# SML-230109PCB1__MCU.net
KiCad netlist of a schematic drawn in Altium Designer
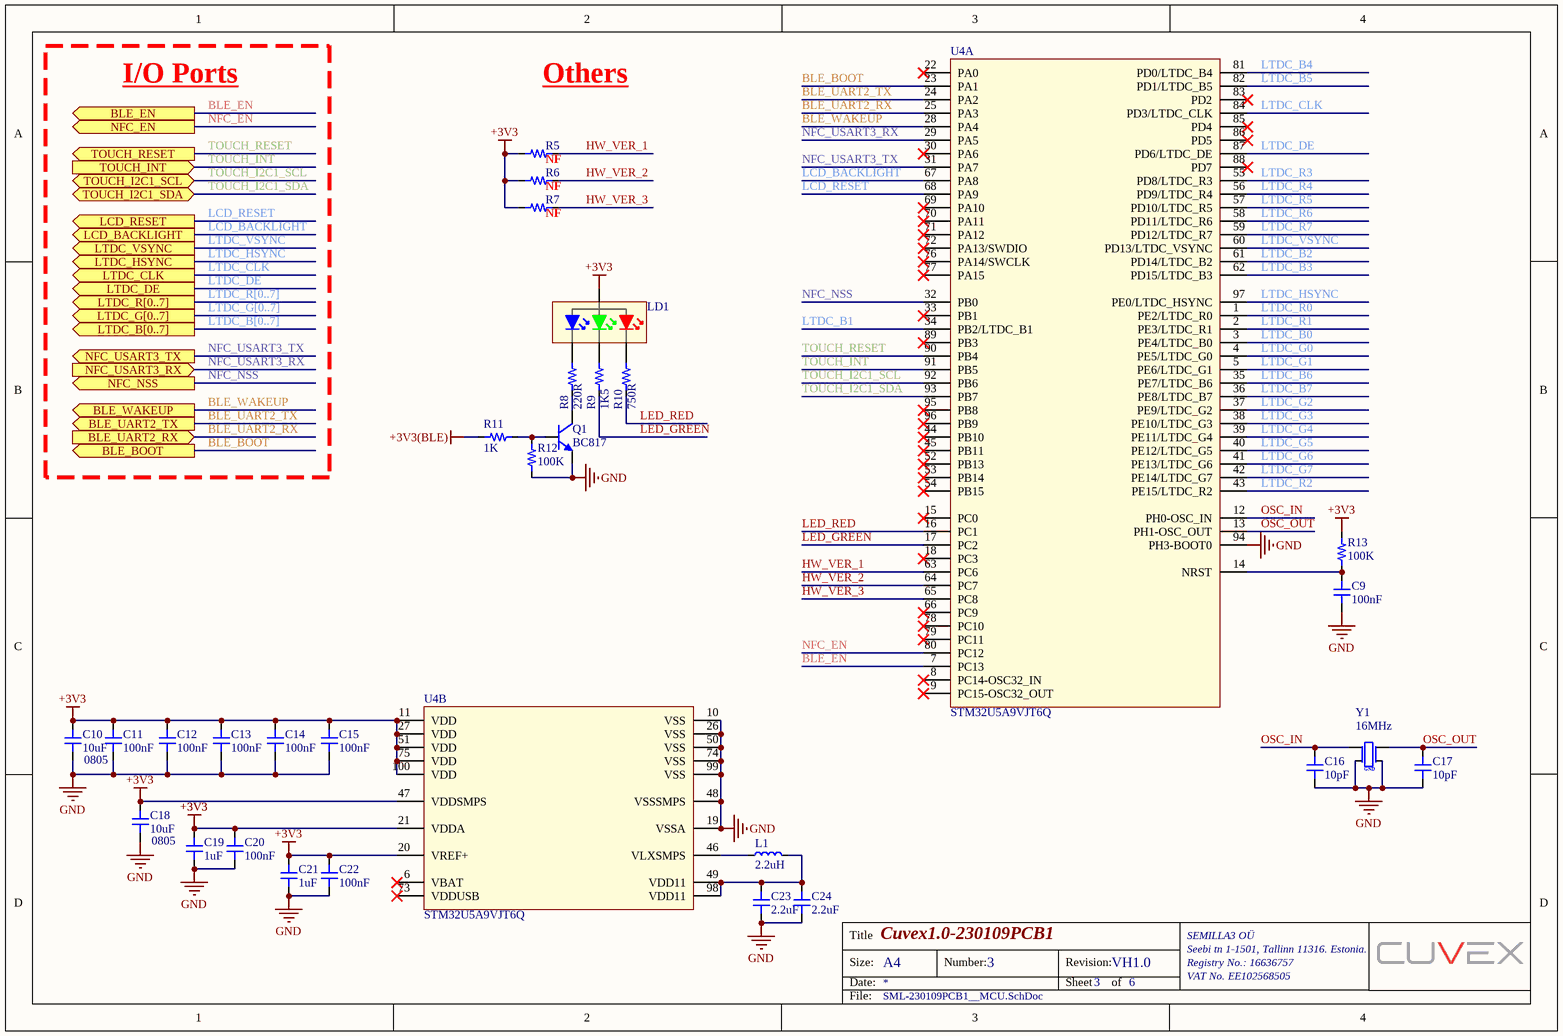
[diagram p0: SML-230109PCB1__MCU.SchDoc]

(export (version "E")
  (design (tool "Eeschema 10.0.6"))
  (components
    (comp (ref "C9")
      (value "100nF")
      (footprint "[G] CAP-MLCC__0603")
      (description "CAP MLCC 0603")
      (fields (field (name "VOLTAGE") "010") (field (name "Comment") "."))
      (libsource (lib "DEB_LIB_SCH_22-03") (part "CAP_MLCC_0603"))
    )
    (comp (ref "C10")
      (value "10uF")
      (footprint "[G] CAP-MLCC__0805")
      (description "CAP MLCC 0805")
      (fields
        (field (name "VOLTAGE") "010")
        (field (name "[06] - PACKAGE") "0805")
        (field (name "Comment") ".")
      )
      (libsource (lib "DEB_LIB_SCH_22-03") (part "CAP_MLCC_0805"))
    )
    (comp (ref "C11")
      (value "100nF")
      (footprint "[G] CAP-MLCC__0603")
      (description "CAP MLCC 0603")
      (fields (field (name "VOLTAGE") "010") (field (name "Comment") "."))
      (libsource (lib "DEB_LIB_SCH_22-03") (part "CAP_MLCC_0603"))
    )
    (comp (ref "C12")
      (value "100nF")
      (footprint "[G] CAP-MLCC__0603")
      (description "CAP MLCC 0603")
      (fields (field (name "VOLTAGE") "010") (field (name "Comment") "."))
      (libsource (lib "DEB_LIB_SCH_22-03") (part "CAP_MLCC_0603"))
    )
    (comp (ref "C13")
      (value "100nF")
      (footprint "[G] CAP-MLCC__0603")
      (description "CAP MLCC 0603")
      (fields (field (name "VOLTAGE") "010") (field (name "Comment") "."))
      (libsource (lib "DEB_LIB_SCH_22-03") (part "CAP_MLCC_0603"))
    )
    (comp (ref "C14")
      (value "100nF")
      (footprint "[G] CAP-MLCC__0603")
      (description "CAP MLCC 0603")
      (fields (field (name "VOLTAGE") "010") (field (name "Comment") "."))
      (libsource (lib "DEB_LIB_SCH_22-03") (part "CAP_MLCC_0603"))
    )
    (comp (ref "C15")
      (value "100nF")
      (footprint "[G] CAP-MLCC__0603")
      (description "CAP MLCC 0603")
      (fields (field (name "VOLTAGE") "010") (field (name "Comment") "."))
      (libsource (lib "DEB_LIB_SCH_22-03") (part "CAP_MLCC_0603"))
    )
    (comp (ref "C16")
      (value "10pF")
      (footprint "[G] CAP-MLCC__0603")
      (description "CAP MLCC 0603")
      (fields (field (name "VOLTAGE") "010") (field (name "Comment") "."))
      (libsource (lib "DEB_LIB_SCH_22-03") (part "CAP_MLCC_0603"))
    )
    (comp (ref "C17")
      (value "10pF")
      (footprint "[G] CAP-MLCC__0603")
      (description "CAP MLCC 0603")
      (fields (field (name "VOLTAGE") "010") (field (name "Comment") "."))
      (libsource (lib "DEB_LIB_SCH_22-03") (part "CAP_MLCC_0603"))
    )
    (comp (ref "C18")
      (value "10uF")
      (footprint "[G] CAP-MLCC__0805")
      (description "CAP MLCC 0805")
      (fields
        (field (name "VOLTAGE") "010")
        (field (name "[06] - PACKAGE") "0805")
        (field (name "Comment") ".")
      )
      (libsource (lib "DEB_LIB_SCH_22-03") (part "CAP_MLCC_0805"))
    )
    (comp (ref "C19")
      (value "1uF")
      (footprint "[G] CAP-MLCC__0603")
      (description "CAP MLCC 0603")
      (fields (field (name "VOLTAGE") "010") (field (name "Comment") "."))
      (libsource (lib "DEB_LIB_SCH_22-03") (part "CAP_MLCC_0603"))
    )
    (comp (ref "C20")
      (value "100nF")
      (footprint "[G] CAP-MLCC__0603")
      (description "CAP MLCC 0603")
      (fields (field (name "VOLTAGE") "010") (field (name "Comment") "."))
      (libsource (lib "DEB_LIB_SCH_22-03") (part "CAP_MLCC_0603"))
    )
    (comp (ref "C21")
      (value "1uF")
      (footprint "[G] CAP-MLCC__0603")
      (description "CAP MLCC 0603")
      (fields (field (name "VOLTAGE") "010") (field (name "Comment") "."))
      (libsource (lib "DEB_LIB_SCH_22-03") (part "CAP_MLCC_0603"))
    )
    (comp (ref "C22")
      (value "100nF")
      (footprint "[G] CAP-MLCC__0603")
      (description "CAP MLCC 0603")
      (fields (field (name "VOLTAGE") "010") (field (name "Comment") "."))
      (libsource (lib "DEB_LIB_SCH_22-03") (part "CAP_MLCC_0603"))
    )
    (comp (ref "C23")
      (value "2.2uF")
      (footprint "[G] CAP-MLCC__0603")
      (description "CAP MLCC 0603")
      (fields (field (name "VOLTAGE") "010") (field (name "Comment") "."))
      (libsource (lib "DEB_LIB_SCH_22-03") (part "CAP_MLCC_0603"))
    )
    (comp (ref "C24")
      (value "2.2uF")
      (footprint "[G] CAP-MLCC__0603")
      (description "CAP MLCC 0603")
      (fields (field (name "VOLTAGE") "010") (field (name "Comment") "."))
      (libsource (lib "DEB_LIB_SCH_22-03") (part "CAP_MLCC_0603"))
    )
    (comp (ref "L1")
      (value "2.2uH")
      (footprint "[G] IND__0603")
      (description "IND SMD 0603 [G]")
      (fields (field (name "Comment") "."))
      (libsource (lib "DEB_LIB_SCH_22-03") (part "IND_SMD_0603"))
    )
    (comp (ref "LD1")
      (value ".")
      (footprint "LED__0603-RGB__APHF1608")
      (description "LED 0603, RGB (621/525/465nm), If=2mA, Vf=1'8-2'65V")
      (libsource (lib "DEB_LIB_SCH_22-03") (part "APHF1608LSEEQBDZGKC"))
    )
    (comp (ref "Q1")
      (value ".")
      (footprint "[G] SOT23-3")
      (description "TRANS BIPOLAR NPN, SOT23-3 [G]")
      (fields (field (name "STAR CODE") "BC817"))
      (libsource (lib "DEB_LIB_SCH_22-03") (part "BC817"))
    )
    (comp (ref "R5")
      (value ".")
      (footprint "[G] RES-CHIP__0603")
      (description "RES SMD 0603 [G]")
      (fields (field (name "TOLERANCE") "1%"))
      (libsource (lib "DEB_LIB_SCH_22-03") (part "RES_SMD_0603"))
    )
    (comp (ref "R6")
      (value ".")
      (footprint "[G] RES-CHIP__0603")
      (description "RES SMD 0603 [G]")
      (fields (field (name "TOLERANCE") "1%"))
      (libsource (lib "DEB_LIB_SCH_22-03") (part "RES_SMD_0603"))
    )
    (comp (ref "R7")
      (value ".")
      (footprint "[G] RES-CHIP__0603")
      (description "RES SMD 0603 [G]")
      (fields (field (name "TOLERANCE") "1%"))
      (libsource (lib "DEB_LIB_SCH_22-03") (part "RES_SMD_0603"))
    )
    (comp (ref "R8")
      (value "220R")
      (footprint "[G] RES-CHIP__0603")
      (description "RES SMD 0603 [G]")
      (fields (field (name "TOLERANCE") "1%") (field (name "Comment") "."))
      (libsource (lib "DEB_LIB_SCH_22-03") (part "RES_SMD_0603"))
    )
    (comp (ref "R9")
      (value "1K5")
      (footprint "[G] RES-CHIP__0603")
      (description "RES SMD 0603 [G]")
      (fields (field (name "TOLERANCE") "1%") (field (name "Comment") "."))
      (libsource (lib "DEB_LIB_SCH_22-03") (part "RES_SMD_0603"))
    )
    (comp (ref "R10")
      (value "750R")
      (footprint "[G] RES-CHIP__0603")
      (description "RES SMD 0603 [G]")
      (fields (field (name "TOLERANCE") "1%") (field (name "Comment") "."))
      (libsource (lib "DEB_LIB_SCH_22-03") (part "RES_SMD_0603"))
    )
    (comp (ref "R11")
      (value "1K")
      (footprint "[G] RES-CHIP__0603")
      (description "RES SMD 0603 [G]")
      (fields (field (name "TOLERANCE") "1%") (field (name "Comment") "."))
      (libsource (lib "DEB_LIB_SCH_22-03") (part "RES_SMD_0603"))
    )
    (comp (ref "R12")
      (value "100K")
      (footprint "[G] RES-CHIP__0603")
      (description "RES SMD 0603 [G]")
      (fields (field (name "TOLERANCE") "1%") (field (name "Comment") "."))
      (libsource (lib "DEB_LIB_SCH_22-03") (part "RES_SMD_0603"))
    )
    (comp (ref "R13")
      (value "100K")
      (footprint "[G] RES-CHIP__0603")
      (description "RES SMD 0603 [G]")
      (fields (field (name "TOLERANCE") "1%") (field (name "Comment") "."))
      (libsource (lib "DEB_LIB_SCH_22-03") (part "RES_SMD_0603"))
    )
    (comp (ref "U4")
      (value ".")
      (footprint "[G] LQFP-100 (14X14MM)")
      (description "MCU ARM 32bit, Cortex-M33 (160MHz), 4MB/2'5MB, LQFP-100 (14x14), SMPS, TrustZone, LTDC, crypto")
      (fields (field (name "[01] - MPN CODE") "STM32U5A9VJT6Q"))
      (libsource (lib "DEB_LIB_SCH_22-03") (part "STM32U5A9VJT6Q"))
    )
    (comp (ref "Y1")
      (value "16MHz")
      (footprint "CRYSTAL__ABM8G")
      (description "CRYSTAL, 16.0000MHz, ±30ppm, CL=10pF, CS=5pF")
      (fields (field (name "Comment") "."))
      (libsource (lib "DEB_LIB_SCH_22-03") (part "ABM8G-16.000MHZ-4Y-T3"))
    )
  )
  (nets
    (net (code "1") (name "+3V3") (class "Default")
      (node (ref "C10") (pin "2") (pinfunction "2_2") (pintype "passive"))
      (node (ref "C11") (pin "2") (pinfunction "2_2") (pintype "passive"))
      (node (ref "C12") (pin "2") (pinfunction "2_2") (pintype "passive"))
      (node (ref "C13") (pin "2") (pinfunction "2_2") (pintype "passive"))
      (node (ref "C14") (pin "2") (pinfunction "2_2") (pintype "passive"))
      (node (ref "C15") (pin "2") (pinfunction "2_2") (pintype "passive"))
      (node (ref "C18") (pin "2") (pinfunction "2_2") (pintype "passive"))
      (node (ref "C19") (pin "1") (pinfunction "1_1") (pintype "passive"))
      (node (ref "C20") (pin "1") (pinfunction "1_1") (pintype "passive"))
      (node (ref "C21") (pin "1") (pinfunction "1_1") (pintype "passive"))
      (node (ref "C22") (pin "1") (pinfunction "1_1") (pintype "passive"))
      (node (ref "LD1") (pin "A") (pinfunction "A_A") (pintype "passive"))
      (node (ref "R13") (pin "1") (pinfunction "1_1") (pintype "passive"))
      (node (ref "R5") (pin "1") (pinfunction "1_1") (pintype "passive"))
      (node (ref "R6") (pin "1") (pinfunction "1_1") (pintype "passive"))
      (node (ref "R7") (pin "1") (pinfunction "1_1") (pintype "passive"))
      (node (ref "U4") (pin "100") (pinfunction "VDD_100") (pintype "passive"))
      (node (ref "U4") (pin "11") (pinfunction "VDD_11") (pintype "passive"))
      (node (ref "U4") (pin "20") (pinfunction "VREF+_20") (pintype "passive"))
      (node (ref "U4") (pin "21") (pinfunction "VDDA_21") (pintype "passive"))
      (node (ref "U4") (pin "27") (pinfunction "VDD_27") (pintype "passive"))
      (node (ref "U4") (pin "47") (pinfunction "VDDSMPS_47") (pintype "passive"))
      (node (ref "U4") (pin "51") (pinfunction "VDD_51") (pintype "passive"))
      (node (ref "U4") (pin "75") (pinfunction "VDD_75") (pintype "passive"))
    )
    (net (code "2") (name "+3V3(BLE)") (class "Default")
      (node (ref "R11") (pin "2") (pinfunction "2_2") (pintype "passive"))
    )
    (net (code "3") (name "/BLE_BOOT") (class "Default")
      (node (ref "U4") (pin "23") (pinfunction "PA1_23") (pintype "passive"))
    )
    (net (code "4") (name "/BLE_EN") (class "Default")
      (node (ref "U4") (pin "7") (pinfunction "PC13_7") (pintype "passive"))
    )
    (net (code "5") (name "/BLE_UART2_RX") (class "Default")
      (node (ref "U4") (pin "25") (pinfunction "PA3_25") (pintype "passive"))
    )
    (net (code "6") (name "/BLE_UART2_TX") (class "Default")
      (node (ref "U4") (pin "24") (pinfunction "PA2_24") (pintype "passive"))
    )
    (net (code "7") (name "/BLE_WAKEUP") (class "Default")
      (node (ref "U4") (pin "28") (pinfunction "PA4_28") (pintype "passive"))
    )
    (net (code "8") (name "/HW_VER_1") (class "Default")
      (node (ref "R5") (pin "2") (pinfunction "2_2") (pintype "passive"))
      (node (ref "U4") (pin "63") (pinfunction "PC6_63") (pintype "passive"))
    )
    (net (code "9") (name "/HW_VER_2") (class "Default")
      (node (ref "R6") (pin "2") (pinfunction "2_2") (pintype "passive"))
      (node (ref "U4") (pin "64") (pinfunction "PC7_64") (pintype "passive"))
    )
    (net (code "10") (name "/HW_VER_3") (class "Default")
      (node (ref "R7") (pin "2") (pinfunction "2_2") (pintype "passive"))
      (node (ref "U4") (pin "65") (pinfunction "PC8_65") (pintype "passive"))
    )
    (net (code "11") (name "/LCD_BACKLIGHT") (class "Default")
      (node (ref "U4") (pin "67") (pinfunction "PA8_67") (pintype "passive"))
    )
    (net (code "12") (name "/LCD_RESET") (class "Default")
      (node (ref "U4") (pin "68") (pinfunction "PA9_68") (pintype "passive"))
    )
    (net (code "13") (name "/LED_GREEN") (class "Default")
      (node (ref "R9") (pin "2") (pinfunction "2_2") (pintype "passive"))
      (node (ref "U4") (pin "17") (pinfunction "PC2_17") (pintype "passive"))
    )
    (net (code "14") (name "/LED_RED") (class "Default")
      (node (ref "R10") (pin "2") (pinfunction "2_2") (pintype "passive"))
      (node (ref "U4") (pin "16") (pinfunction "PC1_16") (pintype "passive"))
    )
    (net (code "15") (name "/LTDC_B0") (class "Default")
      (node (ref "U4") (pin "3") (pinfunction "PE4/LTDC_B0_3") (pintype "passive"))
    )
    (net (code "16") (name "/LTDC_B1") (class "Default")
      (node (ref "U4") (pin "34") (pinfunction "PB2/LTDC_B1_34") (pintype "passive"))
    )
    (net (code "17") (name "/LTDC_B2") (class "Default")
      (node (ref "U4") (pin "61") (pinfunction "PD14/LTDC_B2_61") (pintype "passive"))
    )
    (net (code "18") (name "/LTDC_B3") (class "Default")
      (node (ref "U4") (pin "62") (pinfunction "PD15/LTDC_B3_62") (pintype "passive"))
    )
    (net (code "19") (name "/LTDC_B4") (class "Default")
      (node (ref "U4") (pin "81") (pinfunction "PD0/LTDC_B4_81") (pintype "passive"))
    )
    (net (code "20") (name "/LTDC_B5") (class "Default")
      (node (ref "U4") (pin "82") (pinfunction "PD1/LTDC_B5_82") (pintype "passive"))
    )
    (net (code "21") (name "/LTDC_B6") (class "Default")
      (node (ref "U4") (pin "35") (pinfunction "PE7/LTDC_B6_35") (pintype "passive"))
    )
    (net (code "22") (name "/LTDC_B7") (class "Default")
      (node (ref "U4") (pin "36") (pinfunction "PE8/LTDC_B7_36") (pintype "passive"))
    )
    (net (code "24") (name "/LTDC_CLK") (class "Default")
      (node (ref "U4") (pin "84") (pinfunction "PD3/LTDC_CLK_84") (pintype "passive"))
    )
    (net (code "25") (name "/LTDC_DE") (class "Default")
      (node (ref "U4") (pin "87") (pinfunction "PD6/LTDC_DE_87") (pintype "passive"))
    )
    (net (code "26") (name "/LTDC_G0") (class "Default")
      (node (ref "U4") (pin "4") (pinfunction "PE5/LTDC_G0_4") (pintype "passive"))
    )
    (net (code "27") (name "/LTDC_G1") (class "Default")
      (node (ref "U4") (pin "5") (pinfunction "PE6/LTDC_G1_5") (pintype "passive"))
    )
    (net (code "28") (name "/LTDC_G2") (class "Default")
      (node (ref "U4") (pin "37") (pinfunction "PE9/LTDC_G2_37") (pintype "passive"))
    )
    (net (code "29") (name "/LTDC_G3") (class "Default")
      (node (ref "U4") (pin "38") (pinfunction "PE10/LTDC_G3_38") (pintype "passive"))
    )
    (net (code "30") (name "/LTDC_G4") (class "Default")
      (node (ref "U4") (pin "39") (pinfunction "PE11/LTDC_G4_39") (pintype "passive"))
    )
    (net (code "31") (name "/LTDC_G5") (class "Default")
      (node (ref "U4") (pin "40") (pinfunction "PE12/LTDC_G5_40") (pintype "passive"))
    )
    (net (code "32") (name "/LTDC_G6") (class "Default")
      (node (ref "U4") (pin "41") (pinfunction "PE13/LTDC_G6_41") (pintype "passive"))
    )
    (net (code "33") (name "/LTDC_G7") (class "Default")
      (node (ref "U4") (pin "42") (pinfunction "PE14/LTDC_G7_42") (pintype "passive"))
    )
    (net (code "35") (name "/LTDC_HSYNC") (class "Default")
      (node (ref "U4") (pin "97") (pinfunction "PE0/LTDC_HSYNC_97") (pintype "passive"))
    )
    (net (code "36") (name "/LTDC_R0") (class "Default")
      (node (ref "U4") (pin "1") (pinfunction "PE2/LTDC_R0_1") (pintype "passive"))
    )
    (net (code "37") (name "/LTDC_R1") (class "Default")
      (node (ref "U4") (pin "2") (pinfunction "PE3/LTDC_R1_2") (pintype "passive"))
    )
    (net (code "38") (name "/LTDC_R2") (class "Default")
      (node (ref "U4") (pin "43") (pinfunction "PE15/LTDC_R2_43") (pintype "passive"))
    )
    (net (code "39") (name "/LTDC_R3") (class "Default")
      (node (ref "U4") (pin "55") (pinfunction "PD8/LTDC_R3_55") (pintype "passive"))
    )
    (net (code "40") (name "/LTDC_R4") (class "Default")
      (node (ref "U4") (pin "56") (pinfunction "PD9/LTDC_R4_56") (pintype "passive"))
    )
    (net (code "41") (name "/LTDC_R5") (class "Default")
      (node (ref "U4") (pin "57") (pinfunction "PD10/LTDC_R5_57") (pintype "passive"))
    )
    (net (code "42") (name "/LTDC_R6") (class "Default")
      (node (ref "U4") (pin "58") (pinfunction "PD11/LTDC_R6_58") (pintype "passive"))
    )
    (net (code "43") (name "/LTDC_R7") (class "Default")
      (node (ref "U4") (pin "59") (pinfunction "PD12/LTDC_R7_59") (pintype "passive"))
    )
    (net (code "45") (name "/LTDC_VSYNC") (class "Default")
      (node (ref "U4") (pin "60") (pinfunction "PD13/LTDC_VSYNC_60") (pintype "passive"))
    )
    (net (code "46") (name "/NFC_EN") (class "Default")
      (node (ref "U4") (pin "80") (pinfunction "PC12_80") (pintype "passive"))
    )
    (net (code "47") (name "/NFC_NSS") (class "Default")
      (node (ref "U4") (pin "32") (pinfunction "PB0_32") (pintype "passive"))
    )
    (net (code "48") (name "/NFC_USART3_RX") (class "Default")
      (node (ref "U4") (pin "29") (pinfunction "PA5_29") (pintype "passive"))
    )
    (net (code "49") (name "/NFC_USART3_TX") (class "Default")
      (node (ref "U4") (pin "31") (pinfunction "PA7_31") (pintype "passive"))
    )
    (net (code "50") (name "/OSC_IN") (class "Default")
      (node (ref "C16") (pin "2") (pinfunction "2_2") (pintype "passive"))
      (node (ref "U4") (pin "12") (pinfunction "PH0-OSC_IN_12") (pintype "passive"))
      (node (ref "Y1") (pin "1") (pinfunction "OSC1_1") (pintype "passive"))
    )
    (net (code "51") (name "/OSC_OUT") (class "Default")
      (node (ref "C17") (pin "2") (pinfunction "2_2") (pintype "passive"))
      (node (ref "U4") (pin "13") (pinfunction "PH1-OSC_OUT_13") (pintype "passive"))
      (node (ref "Y1") (pin "3") (pinfunction "OSC2_3") (pintype "passive"))
    )
    (net (code "52") (name "/TOUCH_I2C1_SCL") (class "Default")
      (node (ref "U4") (pin "92") (pinfunction "PB6_92") (pintype "passive"))
    )
    (net (code "53") (name "/TOUCH_I2C1_SDA") (class "Default")
      (node (ref "U4") (pin "93") (pinfunction "PB7_93") (pintype "passive"))
    )
    (net (code "54") (name "/TOUCH_INT") (class "Default")
      (node (ref "U4") (pin "91") (pinfunction "PB5_91") (pintype "passive"))
    )
    (net (code "55") (name "/TOUCH_RESET") (class "Default")
      (node (ref "U4") (pin "90") (pinfunction "PB4_90") (pintype "passive"))
    )
    (net (code "56") (name "GND") (class "Default")
      (node (ref "C10") (pin "1") (pinfunction "1_1") (pintype "passive"))
      (node (ref "C11") (pin "1") (pinfunction "1_1") (pintype "passive"))
      (node (ref "C12") (pin "1") (pinfunction "1_1") (pintype "passive"))
      (node (ref "C13") (pin "1") (pinfunction "1_1") (pintype "passive"))
      (node (ref "C14") (pin "1") (pinfunction "1_1") (pintype "passive"))
      (node (ref "C15") (pin "1") (pinfunction "1_1") (pintype "passive"))
      (node (ref "C16") (pin "1") (pinfunction "1_1") (pintype "passive"))
      (node (ref "C17") (pin "1") (pinfunction "1_1") (pintype "passive"))
      (node (ref "C18") (pin "1") (pinfunction "1_1") (pintype "passive"))
      (node (ref "C19") (pin "2") (pinfunction "2_2") (pintype "passive"))
      (node (ref "C20") (pin "2") (pinfunction "2_2") (pintype "passive"))
      (node (ref "C21") (pin "2") (pinfunction "2_2") (pintype "passive"))
      (node (ref "C22") (pin "2") (pinfunction "2_2") (pintype "passive"))
      (node (ref "C23") (pin "1") (pinfunction "1_1") (pintype "passive"))
      (node (ref "C24") (pin "1") (pinfunction "1_1") (pintype "passive"))
      (node (ref "C9") (pin "2") (pinfunction "2_2") (pintype "passive"))
      (node (ref "Q1") (pin "2") (pinfunction "E_2") (pintype "passive"))
      (node (ref "R12") (pin "1") (pinfunction "1_1") (pintype "passive"))
      (node (ref "U4") (pin "10") (pinfunction "VSS_10") (pintype "passive"))
      (node (ref "U4") (pin "19") (pinfunction "VSSA_19") (pintype "passive"))
      (node (ref "U4") (pin "26") (pinfunction "VSS_26") (pintype "passive"))
      (node (ref "U4") (pin "48") (pinfunction "VSSSMPS_48") (pintype "passive"))
      (node (ref "U4") (pin "50") (pinfunction "VSS_50") (pintype "passive"))
      (node (ref "U4") (pin "74") (pinfunction "VSS_74") (pintype "passive"))
      (node (ref "U4") (pin "94") (pinfunction "PH3-BOOT0_94") (pintype "passive"))
      (node (ref "U4") (pin "99") (pinfunction "VSS_99") (pintype "passive"))
      (node (ref "Y1") (pin "2") (pinfunction "gnd_2") (pintype "passive"))
      (node (ref "Y1") (pin "4") (pinfunction "gnd_4") (pintype "passive"))
    )
    (net (code "57") (name "Net-(C23-Pad2)") (class "Default")
      (node (ref "C23") (pin "2") (pinfunction "2_2") (pintype "passive"))
      (node (ref "C24") (pin "2") (pinfunction "2_2") (pintype "passive"))
      (node (ref "L1") (pin "2") (pinfunction "2_2") (pintype "passive"))
      (node (ref "U4") (pin "49") (pinfunction "VDD11_49") (pintype "passive"))
      (node (ref "U4") (pin "98") (pinfunction "VDD11_98") (pintype "passive"))
    )
    (net (code "58") (name "Net-(LD1-PadKB)") (class "Default")
      (node (ref "LD1") (pin "KB") (pinfunction "KB_KB") (pintype "passive"))
      (node (ref "R8") (pin "2") (pinfunction "2_2") (pintype "passive"))
    )
    (net (code "59") (name "Net-(LD1-PadKG)") (class "Default")
      (node (ref "LD1") (pin "KG") (pinfunction "KG_KG") (pintype "passive"))
      (node (ref "R9") (pin "1") (pinfunction "1_1") (pintype "passive"))
    )
    (net (code "60") (name "Net-(LD1-PadKR)") (class "Default")
      (node (ref "LD1") (pin "KR") (pinfunction "KR_KR") (pintype "passive"))
      (node (ref "R10") (pin "1") (pinfunction "1_1") (pintype "passive"))
    )
    (net (code "61") (name "Net-(Q1-B)") (class "Default")
      (node (ref "Q1") (pin "1") (pinfunction "B_1") (pintype "passive"))
      (node (ref "R11") (pin "1") (pinfunction "1_1") (pintype "passive"))
      (node (ref "R12") (pin "2") (pinfunction "2_2") (pintype "passive"))
    )
    (net (code "62") (name "Net-(Q1-C)") (class "Default")
      (node (ref "Q1") (pin "3") (pinfunction "C_3") (pintype "passive"))
      (node (ref "R8") (pin "1") (pinfunction "1_1") (pintype "passive"))
    )
    (net (code "63") (name "Net-(U4A-NRST)") (class "Default")
      (node (ref "C9") (pin "1") (pinfunction "1_1") (pintype "passive"))
      (node (ref "R13") (pin "2") (pinfunction "2_2") (pintype "passive"))
      (node (ref "U4") (pin "14") (pinfunction "NRST_14") (pintype "passive"))
    )
    (net (code "64") (name "Net-(U4B-VLXSMPS)") (class "Default")
      (node (ref "L1") (pin "1") (pinfunction "1_1") (pintype "passive"))
      (node (ref "U4") (pin "46") (pinfunction "VLXSMPS_46") (pintype "passive"))
    )
    (net (code "65") (name "unconnected-(U4A-PA0-Pad22)") (class "Default")
      (node (ref "U4") (pin "22") (pinfunction "PA0_22") (pintype "passive+no_connect"))
    )
    (net (code "66") (name "unconnected-(U4A-PA6-Pad30)") (class "Default")
      (node (ref "U4") (pin "30") (pinfunction "PA6_30") (pintype "passive+no_connect"))
    )
    (net (code "67") (name "unconnected-(U4A-PA10-Pad69)") (class "Default")
      (node (ref "U4") (pin "69") (pinfunction "PA10_69") (pintype "passive+no_connect"))
    )
    (net (code "68") (name "unconnected-(U4A-PA11-Pad70)") (class "Default")
      (node (ref "U4") (pin "70") (pinfunction "PA11_70") (pintype "passive+no_connect"))
    )
    (net (code "69") (name "unconnected-(U4A-PA12-Pad71)") (class "Default")
      (node (ref "U4") (pin "71") (pinfunction "PA12_71") (pintype "passive+no_connect"))
    )
    (net (code "70") (name "unconnected-(U4A-PA13{slash}SWDIO-Pad72)") (class "Default")
      (node (ref "U4") (pin "72") (pinfunction "PA13/SWDIO_72") (pintype "passive+no_connect"))
    )
    (net (code "71") (name "unconnected-(U4A-PA14{slash}SWCLK-Pad76)") (class "Default")
      (node (ref "U4") (pin "76") (pinfunction "PA14/SWCLK_76") (pintype "passive+no_connect"))
    )
    (net (code "72") (name "unconnected-(U4A-PA15-Pad77)") (class "Default")
      (node (ref "U4") (pin "77") (pinfunction "PA15_77") (pintype "passive+no_connect"))
    )
    (net (code "73") (name "unconnected-(U4A-PB1-Pad33)") (class "Default")
      (node (ref "U4") (pin "33") (pinfunction "PB1_33") (pintype "passive+no_connect"))
    )
    (net (code "74") (name "unconnected-(U4A-PB3-Pad89)") (class "Default")
      (node (ref "U4") (pin "89") (pinfunction "PB3_89") (pintype "passive+no_connect"))
    )
    (net (code "75") (name "unconnected-(U4A-PB8-Pad95)") (class "Default")
      (node (ref "U4") (pin "95") (pinfunction "PB8_95") (pintype "passive+no_connect"))
    )
    (net (code "76") (name "unconnected-(U4A-PB9-Pad96)") (class "Default")
      (node (ref "U4") (pin "96") (pinfunction "PB9_96") (pintype "passive+no_connect"))
    )
    (net (code "77") (name "unconnected-(U4A-PB10-Pad44)") (class "Default")
      (node (ref "U4") (pin "44") (pinfunction "PB10_44") (pintype "passive+no_connect"))
    )
    (net (code "78") (name "unconnected-(U4A-PB11-Pad45)") (class "Default")
      (node (ref "U4") (pin "45") (pinfunction "PB11_45") (pintype "passive+no_connect"))
    )
    (net (code "79") (name "unconnected-(U4A-PB13-Pad52)") (class "Default")
      (node (ref "U4") (pin "52") (pinfunction "PB13_52") (pintype "passive+no_connect"))
    )
    (net (code "80") (name "unconnected-(U4A-PB14-Pad53)") (class "Default")
      (node (ref "U4") (pin "53") (pinfunction "PB14_53") (pintype "passive+no_connect"))
    )
    (net (code "81") (name "unconnected-(U4A-PB15-Pad54)") (class "Default")
      (node (ref "U4") (pin "54") (pinfunction "PB15_54") (pintype "passive+no_connect"))
    )
    (net (code "82") (name "unconnected-(U4A-PC0-Pad15)") (class "Default")
      (node (ref "U4") (pin "15") (pinfunction "PC0_15") (pintype "passive+no_connect"))
    )
    (net (code "83") (name "unconnected-(U4A-PC3-Pad18)") (class "Default")
      (node (ref "U4") (pin "18") (pinfunction "PC3_18") (pintype "passive+no_connect"))
    )
    (net (code "84") (name "unconnected-(U4A-PC9-Pad66)") (class "Default")
      (node (ref "U4") (pin "66") (pinfunction "PC9_66") (pintype "passive+no_connect"))
    )
    (net (code "85") (name "unconnected-(U4A-PC10-Pad78)") (class "Default")
      (node (ref "U4") (pin "78") (pinfunction "PC10_78") (pintype "passive+no_connect"))
    )
    (net (code "86") (name "unconnected-(U4A-PC11-Pad79)") (class "Default")
      (node (ref "U4") (pin "79") (pinfunction "PC11_79") (pintype "passive+no_connect"))
    )
    (net (code "87") (name "unconnected-(U4A-PC14-OSC32_IN-Pad8)") (class "Default")
      (node (ref "U4") (pin "8") (pinfunction "PC14-OSC32_IN_8") (pintype "passive+no_connect"))
    )
    (net (code "88") (name "unconnected-(U4A-PC15-OSC32_OUT-Pad9)") (class "Default")
      (node (ref "U4") (pin "9") (pinfunction "PC15-OSC32_OUT_9") (pintype "passive+no_connect"))
    )
    (net (code "89") (name "unconnected-(U4A-PD2-Pad83)") (class "Default")
      (node (ref "U4") (pin "83") (pinfunction "PD2_83") (pintype "passive+no_connect"))
    )
    (net (code "90") (name "unconnected-(U4A-PD4-Pad85)") (class "Default")
      (node (ref "U4") (pin "85") (pinfunction "PD4_85") (pintype "passive+no_connect"))
    )
    (net (code "91") (name "unconnected-(U4A-PD5-Pad86)") (class "Default")
      (node (ref "U4") (pin "86") (pinfunction "PD5_86") (pintype "passive+no_connect"))
    )
    (net (code "92") (name "unconnected-(U4A-PD7-Pad88)") (class "Default")
      (node (ref "U4") (pin "88") (pinfunction "PD7_88") (pintype "passive+no_connect"))
    )
    (net (code "93") (name "unconnected-(U4B-VBAT-Pad6)") (class "Default")
      (node (ref "U4") (pin "6") (pinfunction "VBAT_6") (pintype "passive+no_connect"))
    )
    (net (code "94") (name "unconnected-(U4B-VDDUSB-Pad73)") (class "Default")
      (node (ref "U4") (pin "73") (pinfunction "VDDUSB_73") (pintype "passive+no_connect"))
    )
  )
)
